# USB.net
KiCad netlist of a schematic drawn in Altium Designer
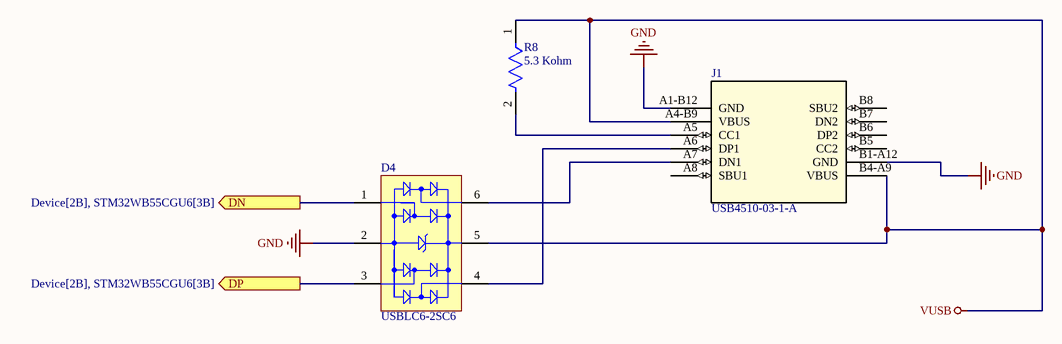
[diagram p0: USB.SchDoc]

(export (version "E")
  (design (tool "Eeschema 10.0.6"))
  (components
    (comp (ref "D4")
      (value "USBLC6-2SC6")
      (footprint "STM-SOT23-6L_V")
      (description "Very low capacitance ESD protection, 3.5 pF, -40 to 125 degC, 6-Pin SOT23, RoHS, Tape and Reel")
      (fields (field (name "MANUFACTURER") "STMicroelectronics"))
      (libsource (lib "Altium Content Vault") (part "STM-USB_DVI_HDMIULC6-4SC6X-SOT23-6L"))
    )
    (comp (ref "J1")
      (value "USB4510-03-1-A")
      (footprint "USB4510-03-1-A_GCT")
      (fields (field (name "COPYRIGHT") "Copyright (C) 2023 Ultra Librarian. All rights reserved."))
      (libsource (lib "ANT") (part "USB4510-03-1-A"))
    )
    (comp (ref "R8")
      (value "5.3 Kohm")
      (footprint "FP-RC1005-IPC_C")
      (description "Res Thick Film 0402 1.87kΩ 1% 0.063W ±100ppm/°C Molded SMD T/R")
      (fields (field (name "TOLERANCE") "1%"))
      (libsource (lib "Altium Content Vault") (part "1029c3af85768c4190bb7ad29bc67b5"))
    )
  )
  (nets
    (net (code "1") (name "/DN") (class "Default")
      (node (ref "D4") (pin "1") (pinfunction "I/O_1_1") (pintype "passive"))
    )
    (net (code "2") (name "/DP") (class "Default")
      (node (ref "D4") (pin "3") (pinfunction "I/O_2_3") (pintype "passive"))
    )
    (net (code "3") (name "GND") (class "Default")
      (node (ref "D4") (pin "2") (pinfunction "GND_2") (pintype "passive"))
      (node (ref "J1") (pin "A1-B12") (pinfunction "GND_A1-B12") (pintype "passive"))
      (node (ref "J1") (pin "B1-A12") (pinfunction "GND_B1-A12") (pintype "passive"))
    )
    (net (code "4") (name "Net-(D4-I{slash}O_3)") (class "Default")
      (node (ref "D4") (pin "4") (pinfunction "I/O_3_4") (pintype "passive"))
      (node (ref "J1") (pin "A6") (pinfunction "DP1_A6") (pintype "bidirectional"))
    )
    (net (code "5") (name "Net-(D4-I{slash}O_4)") (class "Default")
      (node (ref "D4") (pin "6") (pinfunction "I/O_4_6") (pintype "passive"))
      (node (ref "J1") (pin "A7") (pinfunction "DN1_A7") (pintype "bidirectional"))
    )
    (net (code "6") (name "Net-(J1-CC1)") (class "Default")
      (node (ref "J1") (pin "A5") (pinfunction "CC1_A5") (pintype "bidirectional"))
      (node (ref "R8") (pin "2") (pinfunction "2_2") (pintype "passive"))
    )
    (net (code "7") (name "VUSB") (class "Default")
      (node (ref "D4") (pin "5") (pinfunction "VBUS_5") (pintype "passive"))
      (node (ref "J1") (pin "A4-B9") (pinfunction "VBUS_A4-B9") (pintype "power_in"))
      (node (ref "J1") (pin "B4-A9") (pinfunction "VBUS_B4-A9") (pintype "power_in"))
      (node (ref "R8") (pin "1") (pinfunction "1_1") (pintype "passive"))
    )
    (net (code "8") (name "unconnected-(J1-CC2-PadB5)") (class "Default")
      (node (ref "J1") (pin "B5") (pinfunction "CC2_B5") (pintype "bidirectional"))
    )
    (net (code "9") (name "unconnected-(J1-DN2-PadB7)") (class "Default")
      (node (ref "J1") (pin "B7") (pinfunction "DN2_B7") (pintype "bidirectional"))
    )
    (net (code "10") (name "unconnected-(J1-DP2-PadB6)") (class "Default")
      (node (ref "J1") (pin "B6") (pinfunction "DP2_B6") (pintype "bidirectional"))
    )
    (net (code "11") (name "unconnected-(J1-SBU1-PadA8)") (class "Default")
      (node (ref "J1") (pin "A8") (pinfunction "SBU1_A8") (pintype "bidirectional"))
    )
    (net (code "12") (name "unconnected-(J1-SBU2-PadB8)") (class "Default")
      (node (ref "J1") (pin "B8") (pinfunction "SBU2_B8") (pintype "bidirectional"))
    )
  )
)
